# RDA5807M_BREAKOUT_SETUP.net
KiCad netlist of a schematic drawn in EAGLE
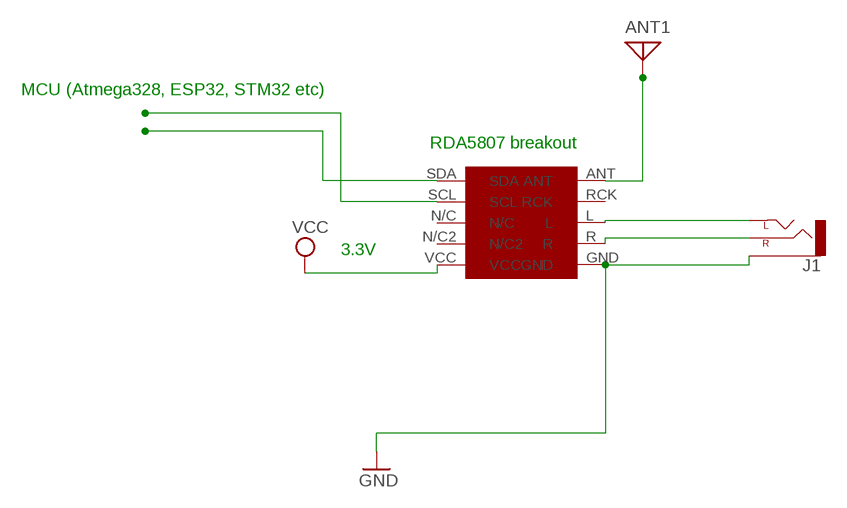
[diagram p0: schematic, sheet 1]

(export (version "E")
  (design (tool "Eeschema 10.0.6"))
  (components
    (comp (ref "ANT1")
      (value "ANTENNA")
      (footprint "eagle-import:PAD-01")
      (libsource (lib "eagle-import") (part "ANTENNA"))
    )
    (comp (ref "J1")
      (value "AUDIO_JACK_2.5MMSPECIAL_POGO_PINS")
      (footprint "eagle-import:STEREOJACK2.5MM_SPECIAL_POGOPINS")
      (libsource (lib "eagle-import") (part "AUDIO_JACK_2.5MMSPECIAL_POGO_PINS"))
    )
    (comp (ref "U$1")
      (value "RDA")
      (footprint "eagle-import:RDA")
      (libsource (lib "eagle-import") (part "RDA"))
    )
  )
  (nets
    (net (code "1") (name "GND") (class "Default")
      (node (ref "J1") (pin "RING1") (pinfunction "SLEEVE_RING1") (pintype "bidirectional"))
      (node (ref "U$1") (pin "GND") (pinfunction "GND_GND") (pintype "power_in"))
    )
    (net (code "2") (name "Net-(ANT1-Pad1)") (class "Default")
      (node (ref "ANT1") (pin "1") (pinfunction "1_1") (pintype "output"))
      (node (ref "U$1") (pin "ANT") (pinfunction "ANT_ANT") (pintype "input"))
    )
    (net (code "3") (name "Net-(J1-LEFT)") (class "Default")
      (node (ref "J1") (pin "SHIELD") (pinfunction "LEFT_SHIELD") (pintype "bidirectional"))
      (node (ref "U$1") (pin "L") (pinfunction "L_L") (pintype "output"))
    )
    (net (code "4") (name "Net-(J1-RIGHT)") (class "Default")
      (node (ref "J1") (pin "TIP") (pinfunction "RIGHT_TIP") (pintype "bidirectional"))
      (node (ref "U$1") (pin "R") (pinfunction "R_R") (pintype "output"))
    )
    (net (code "5") (name "VCC") (class "Default")
      (node (ref "U$1") (pin "VCC") (pinfunction "VCC_VCC") (pintype "power_in"))
    )
    (net (code "6") (name "unconnected-(U$1-PadN{slash}C)") (class "Default")
      (node (ref "U$1") (pin "N/C") (pinfunction "N/C_N/C") (pintype "passive"))
    )
    (net (code "7") (name "unconnected-(U$1-PadN{slash}C2)") (class "Default")
      (node (ref "U$1") (pin "N/C2") (pinfunction "N/C2_N/C2") (pintype "passive"))
    )
    (net (code "8") (name "unconnected-(U$1-PadRCK)") (class "Default")
      (node (ref "U$1") (pin "RCK") (pinfunction "RCK_RCK") (pintype "bidirectional"))
    )
    (net (code "9") (name "unconnected-(U$1-PadSCL)") (class "Default")
      (node (ref "U$1") (pin "SCL") (pinfunction "SCL_SCL") (pintype "bidirectional"))
    )
    (net (code "10") (name "unconnected-(U$1-PadSDA)") (class "Default")
      (node (ref "U$1") (pin "SDA") (pinfunction "SDA_SDA") (pintype "bidirectional"))
    )
  )
)
